# rs232RGBLEDController.net
KiCad netlist of a schematic drawn in EAGLE
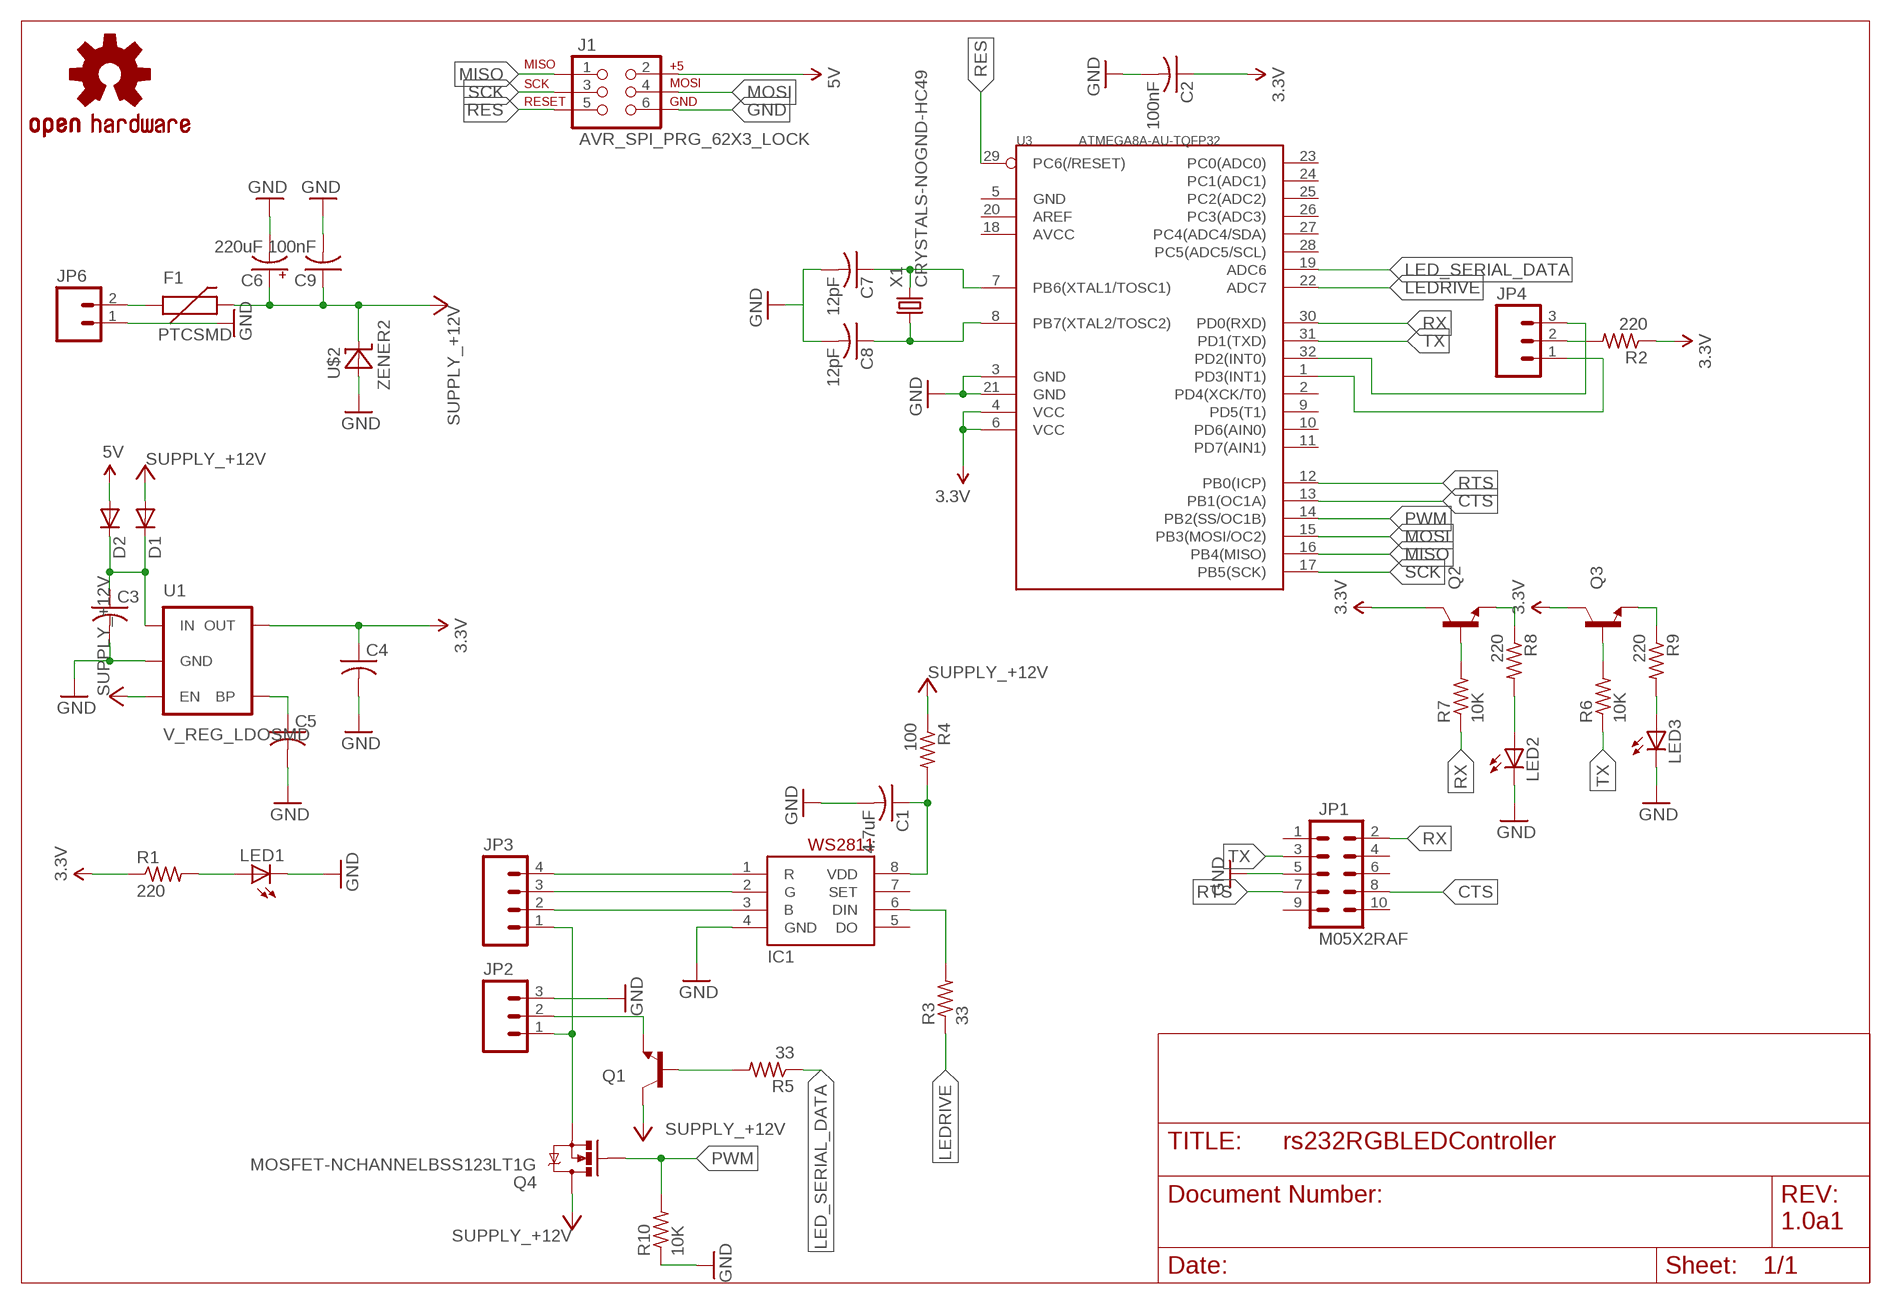
[diagram p0: schematic, sheet 1]

(export (version "E")
  (design (tool "Eeschema 10.0.6"))
  (components
    (comp (ref "C1")
      (value "4.7uF")
      (footprint "eagle-import:C0603")
      (libsource (lib "eagle-import") (part "C-USC0603"))
    )
    (comp (ref "C2")
      (value "100nF")
      (footprint "eagle-import:C0603")
      (libsource (lib "eagle-import") (part "C-USC0603"))
    )
    (comp (ref "C3")
      (value "C-USC0603")
      (footprint "eagle-import:C0603")
      (libsource (lib "eagle-import") (part "C-USC0603"))
    )
    (comp (ref "C4")
      (value "C-USC0603")
      (footprint "eagle-import:C0603")
      (libsource (lib "eagle-import") (part "C-USC0603"))
    )
    (comp (ref "C5")
      (value "C-USC0603")
      (footprint "eagle-import:C0603")
      (libsource (lib "eagle-import") (part "C-USC0603"))
    )
    (comp (ref "C6")
      (value "220uF")
      (footprint "eagle-import:175TMP-0810")
      (libsource (lib "eagle-import") (part "CPOL-US175TMP-0810"))
    )
    (comp (ref "C7")
      (value "12pF")
      (footprint "eagle-import:C0603")
      (libsource (lib "eagle-import") (part "C-USC0603"))
    )
    (comp (ref "C8")
      (value "12pF")
      (footprint "eagle-import:C0603")
      (libsource (lib "eagle-import") (part "C-USC0603"))
    )
    (comp (ref "C9")
      (value "100nF")
      (footprint "eagle-import:C0603")
      (libsource (lib "eagle-import") (part "C-USC0603"))
    )
    (comp (ref "D1")
      (value "DIODESOT23")
      (footprint "eagle-import:SOT23-3")
      (libsource (lib "eagle-import") (part "DIODESOT23"))
    )
    (comp (ref "D2")
      (value "DIODESOT23")
      (footprint "eagle-import:SOT23-3")
      (libsource (lib "eagle-import") (part "DIODESOT23"))
    )
    (comp (ref "F1")
      (value "PTCSMD")
      (footprint "eagle-import:PTC-1206")
      (libsource (lib "eagle-import") (part "PTCSMD"))
    )
    (comp (ref "IC1")
      (value "WS2811-SOP8")
      (footprint "eagle-import:SO08-SKINNYPADS")
      (libsource (lib "eagle-import") (part "WS2811-SOP8"))
    )
    (comp (ref "J1")
      (value "AVR_SPI_PRG_62X3_LOCK")
      (footprint "eagle-import:2X3_LOCK")
      (libsource (lib "eagle-import") (part "AVR_SPI_PRG_62X3_LOCK"))
    )
    (comp (ref "JP1")
      (value "M05X2RAF")
      (footprint "eagle-import:2X5-RAF")
      (libsource (lib "eagle-import") (part "M05X2RAF"))
    )
    (comp (ref "JP2")
      (value "M03PTH")
      (footprint "eagle-import:1X03")
      (libsource (lib "eagle-import") (part "M03PTH"))
    )
    (comp (ref "JP3")
      (value "M04PTH")
      (footprint "eagle-import:1X04")
      (libsource (lib "eagle-import") (part "M04PTH"))
    )
    (comp (ref "JP4")
      (value "M03PTH")
      (footprint "eagle-import:1X03")
      (libsource (lib "eagle-import") (part "M03PTH"))
    )
    (comp (ref "JP6")
      (value "M021X02_NO_SILK")
      (footprint "eagle-import:1X02_NO_SILK")
      (libsource (lib "eagle-import") (part "M021X02_NO_SILK"))
    )
    (comp (ref "LED1")
      (value "LED0603")
      (footprint "eagle-import:LED-0603")
      (libsource (lib "eagle-import") (part "LED0603"))
    )
    (comp (ref "LED2")
      (value "LED0603")
      (footprint "eagle-import:LED-0603")
      (libsource (lib "eagle-import") (part "LED0603"))
    )
    (comp (ref "LED3")
      (value "LED0603")
      (footprint "eagle-import:LED-0603")
      (libsource (lib "eagle-import") (part "LED0603"))
    )
    (comp (ref "Q1")
      (value "TRANSISTOR_NPNSOT23")
      (footprint "eagle-import:SOT23")
      (libsource (lib "eagle-import") (part "TRANSISTOR_NPNSOT23"))
    )
    (comp (ref "Q2")
      (value "TRANSISTOR_NPNSOT23")
      (footprint "eagle-import:SOT23")
      (libsource (lib "eagle-import") (part "TRANSISTOR_NPNSOT23"))
    )
    (comp (ref "Q3")
      (value "TRANSISTOR_NPNSOT23")
      (footprint "eagle-import:SOT23")
      (libsource (lib "eagle-import") (part "TRANSISTOR_NPNSOT23"))
    )
    (comp (ref "Q4")
      (value "MOSFET-NCHANNELBSS123LT1G")
      (footprint "eagle-import:SOT23-3")
      (libsource (lib "eagle-import") (part "MOSFET-NCHANNELBSS123LT1G"))
    )
    (comp (ref "R1")
      (value "220")
      (footprint "eagle-import:R0603")
      (libsource (lib "eagle-import") (part "R-US_R0603"))
    )
    (comp (ref "R2")
      (value "220")
      (footprint "eagle-import:R0603")
      (libsource (lib "eagle-import") (part "R-US_R0603"))
    )
    (comp (ref "R3")
      (value "33")
      (footprint "eagle-import:R0603")
      (libsource (lib "eagle-import") (part "R-US_R0603"))
    )
    (comp (ref "R4")
      (value "100")
      (footprint "eagle-import:R0603")
      (libsource (lib "eagle-import") (part "R-US_R0603"))
    )
    (comp (ref "R5")
      (value "33")
      (footprint "eagle-import:R0603")
      (libsource (lib "eagle-import") (part "R-US_R0603"))
    )
    (comp (ref "R6")
      (value "10K")
      (footprint "eagle-import:R0603")
      (libsource (lib "eagle-import") (part "R-US_R0603"))
    )
    (comp (ref "R7")
      (value "10K")
      (footprint "eagle-import:R0603")
      (libsource (lib "eagle-import") (part "R-US_R0603"))
    )
    (comp (ref "R8")
      (value "220")
      (footprint "eagle-import:R0603")
      (libsource (lib "eagle-import") (part "R-US_R0603"))
    )
    (comp (ref "R9")
      (value "220")
      (footprint "eagle-import:R0603")
      (libsource (lib "eagle-import") (part "R-US_R0603"))
    )
    (comp (ref "R10")
      (value "10K")
      (footprint "eagle-import:R0603")
      (libsource (lib "eagle-import") (part "R-US_R0603"))
    )
    (comp (ref "U$1")
      (value "OSHW-LOGOS")
      (footprint "eagle-import:OSHW-LOGO-S")
      (libsource (lib "eagle-import") (part "OSHW-LOGOS"))
    )
    (comp (ref "U$2")
      (value "ZENER2")
      (footprint "eagle-import:SOD123")
      (fields (field (name "SPICEPREFIX") "B"))
      (libsource (lib "eagle-import") (part "ZENER2"))
    )
    (comp (ref "U1")
      (value "V_REG_LDOSMD")
      (footprint "eagle-import:SOT23-5")
      (libsource (lib "eagle-import") (part "V_REG_LDOSMD"))
    )
    (comp (ref "U3")
      (value "ATMEGA8A-AU-TQFP32")
      (footprint "eagle-import:TQFP32-0.8-7X7MM")
      (fields (field (name "MPN") "ATMEGA8A-AU"))
      (libsource (lib "eagle-import") (part "MCU-ATMEGA8A-AU(TQFP32)"))
    )
    (comp (ref "X1")
      (value "CRYSTALS-NOGND-HC49")
      (footprint "eagle-import:HC49")
      (libsource (lib "eagle-import") (part "CRYSTALS-NOGND-HC49"))
    )
  )
  (nets
    (net (code "1") (name "3.3V") (class "Default")
      (node (ref "C2") (pin "1") (pinfunction "1_1") (pintype "passive"))
      (node (ref "C4") (pin "1") (pinfunction "1_1") (pintype "passive"))
      (node (ref "Q2") (pin "3") (pinfunction "C_3") (pintype "passive"))
      (node (ref "Q3") (pin "3") (pinfunction "C_3") (pintype "passive"))
      (node (ref "R1") (pin "1") (pinfunction "1_1") (pintype "passive"))
      (node (ref "R2") (pin "1") (pinfunction "1_1") (pintype "passive"))
      (node (ref "U1") (pin "5") (pinfunction "OUT_5") (pintype "passive"))
      (node (ref "U3") (pin "4") (pinfunction "VCC_4") (pintype "bidirectional"))
      (node (ref "U3") (pin "6") (pinfunction "VCC_6") (pintype "bidirectional"))
    )
    (net (code "2") (name "5V") (class "Default")
      (node (ref "D2") (pin "1") (pinfunction "A_1") (pintype "passive"))
      (node (ref "J1") (pin "2") (pinfunction "2_2") (pintype "passive"))
    )
    (net (code "3") (name "CTS") (class "Default")
      (node (ref "JP1") (pin "8") (pinfunction "8_8") (pintype "passive"))
      (node (ref "U3") (pin "13") (pinfunction "PB1(OC1A)_13") (pintype "bidirectional"))
    )
    (net (code "4") (name "GND") (class "Default")
      (node (ref "C1") (pin "2") (pinfunction "2_2") (pintype "passive"))
      (node (ref "C2") (pin "2") (pinfunction "2_2") (pintype "passive"))
      (node (ref "C3") (pin "2") (pinfunction "2_2") (pintype "passive"))
      (node (ref "C4") (pin "2") (pinfunction "2_2") (pintype "passive"))
      (node (ref "C5") (pin "2") (pinfunction "2_2") (pintype "passive"))
      (node (ref "C6") (pin "-") (pinfunction "-_-") (pintype "passive"))
      (node (ref "C7") (pin "2") (pinfunction "2_2") (pintype "passive"))
      (node (ref "C8") (pin "2") (pinfunction "2_2") (pintype "passive"))
      (node (ref "C9") (pin "2") (pinfunction "2_2") (pintype "passive"))
      (node (ref "IC1") (pin "4") (pinfunction "GND_4") (pintype "power_in"))
      (node (ref "J1") (pin "6") (pinfunction "6_6") (pintype "passive"))
      (node (ref "JP1") (pin "5") (pinfunction "5_5") (pintype "passive"))
      (node (ref "JP2") (pin "3") (pinfunction "3_3") (pintype "passive"))
      (node (ref "JP6") (pin "1") (pinfunction "1_1") (pintype "passive"))
      (node (ref "LED1") (pin "C") (pinfunction "C_C") (pintype "passive"))
      (node (ref "LED2") (pin "C") (pinfunction "C_C") (pintype "passive"))
      (node (ref "LED3") (pin "C") (pinfunction "C_C") (pintype "passive"))
      (node (ref "R10") (pin "1") (pinfunction "1_1") (pintype "passive"))
      (node (ref "U$2") (pin "A") (pinfunction "A_A") (pintype "passive"))
      (node (ref "U1") (pin "2") (pinfunction "GND_2") (pintype "input"))
      (node (ref "U3") (pin "21") (pinfunction "GND_21") (pintype "bidirectional"))
      (node (ref "U3") (pin "3") (pinfunction "GND_3") (pintype "bidirectional"))
    )
    (net (code "5") (name "LEDRIVE") (class "Default")
      (node (ref "R3") (pin "1") (pinfunction "1_1") (pintype "passive"))
      (node (ref "U3") (pin "22") (pinfunction "ADC7_22") (pintype "bidirectional"))
    )
    (net (code "6") (name "LED_SERIAL_DATA") (class "Default")
      (node (ref "R5") (pin "1") (pinfunction "1_1") (pintype "passive"))
      (node (ref "U3") (pin "19") (pinfunction "ADC6_19") (pintype "bidirectional"))
    )
    (net (code "7") (name "MISO") (class "Default")
      (node (ref "J1") (pin "1") (pinfunction "1_1") (pintype "passive"))
      (node (ref "U3") (pin "16") (pinfunction "PB4(MISO)_16") (pintype "bidirectional"))
    )
    (net (code "8") (name "MOSI") (class "Default")
      (node (ref "J1") (pin "4") (pinfunction "4_4") (pintype "passive"))
      (node (ref "U3") (pin "15") (pinfunction "PB3(MOSI/OC2)_15") (pintype "bidirectional"))
    )
    (net (code "9") (name "Net-(D1-C)") (class "Default")
      (node (ref "C3") (pin "1") (pinfunction "1_1") (pintype "passive"))
      (node (ref "D1") (pin "3") (pinfunction "C_3") (pintype "passive"))
      (node (ref "D2") (pin "3") (pinfunction "C_3") (pintype "passive"))
      (node (ref "U1") (pin "1") (pinfunction "IN_1") (pintype "input"))
    )
    (net (code "10") (name "Net-(F1-Pad1)") (class "Default")
      (node (ref "F1") (pin "1") (pinfunction "1_1") (pintype "bidirectional"))
      (node (ref "JP6") (pin "2") (pinfunction "2_2") (pintype "passive"))
    )
    (net (code "11") (name "Net-(IC1-B)") (class "Default")
      (node (ref "IC1") (pin "3") (pinfunction "B_3") (pintype "open_collector"))
      (node (ref "JP3") (pin "2") (pinfunction "2_2") (pintype "passive"))
    )
    (net (code "12") (name "Net-(IC1-DIN)") (class "Default")
      (node (ref "IC1") (pin "6") (pinfunction "DIN_6") (pintype "input"))
      (node (ref "R3") (pin "2") (pinfunction "2_2") (pintype "passive"))
    )
    (net (code "13") (name "Net-(IC1-G)") (class "Default")
      (node (ref "IC1") (pin "2") (pinfunction "G_2") (pintype "open_collector"))
      (node (ref "JP3") (pin "3") (pinfunction "3_3") (pintype "passive"))
    )
    (net (code "14") (name "Net-(IC1-R)") (class "Default")
      (node (ref "IC1") (pin "1") (pinfunction "R_1") (pintype "open_collector"))
      (node (ref "JP3") (pin "4") (pinfunction "4_4") (pintype "passive"))
    )
    (net (code "15") (name "Net-(IC1-VDD)") (class "Default")
      (node (ref "C1") (pin "1") (pinfunction "1_1") (pintype "passive"))
      (node (ref "IC1") (pin "8") (pinfunction "VDD_8") (pintype "power_in"))
      (node (ref "R4") (pin "2") (pinfunction "2_2") (pintype "passive"))
    )
    (net (code "16") (name "Net-(JP4-Pad2)") (class "Default")
      (node (ref "JP4") (pin "2") (pinfunction "2_2") (pintype "passive"))
      (node (ref "R2") (pin "2") (pinfunction "2_2") (pintype "passive"))
    )
    (net (code "17") (name "Net-(LED1-PadA)") (class "Default")
      (node (ref "LED1") (pin "A") (pinfunction "A_A") (pintype "passive"))
      (node (ref "R1") (pin "2") (pinfunction "2_2") (pintype "passive"))
    )
    (net (code "18") (name "Net-(LED2-PadA)") (class "Default")
      (node (ref "LED2") (pin "A") (pinfunction "A_A") (pintype "passive"))
      (node (ref "R8") (pin "2") (pinfunction "2_2") (pintype "passive"))
    )
    (net (code "19") (name "Net-(LED3-PadA)") (class "Default")
      (node (ref "LED3") (pin "A") (pinfunction "A_A") (pintype "passive"))
      (node (ref "R9") (pin "2") (pinfunction "2_2") (pintype "passive"))
    )
    (net (code "20") (name "Net-(Q1-B)") (class "Default")
      (node (ref "Q1") (pin "1") (pinfunction "B_1") (pintype "passive"))
      (node (ref "R5") (pin "2") (pinfunction "2_2") (pintype "passive"))
    )
    (net (code "21") (name "Net-(Q1-E)") (class "Default")
      (node (ref "JP2") (pin "2") (pinfunction "2_2") (pintype "passive"))
      (node (ref "Q1") (pin "2") (pinfunction "E_2") (pintype "passive"))
    )
    (net (code "22") (name "Net-(Q2-B)") (class "Default")
      (node (ref "Q2") (pin "1") (pinfunction "B_1") (pintype "passive"))
      (node (ref "R7") (pin "2") (pinfunction "2_2") (pintype "passive"))
    )
    (net (code "23") (name "Net-(Q2-E)") (class "Default")
      (node (ref "Q2") (pin "2") (pinfunction "E_2") (pintype "passive"))
      (node (ref "R8") (pin "1") (pinfunction "1_1") (pintype "passive"))
    )
    (net (code "24") (name "Net-(Q3-B)") (class "Default")
      (node (ref "Q3") (pin "1") (pinfunction "B_1") (pintype "passive"))
      (node (ref "R6") (pin "2") (pinfunction "2_2") (pintype "passive"))
    )
    (net (code "25") (name "Net-(Q3-E)") (class "Default")
      (node (ref "Q3") (pin "2") (pinfunction "E_2") (pintype "passive"))
      (node (ref "R9") (pin "1") (pinfunction "1_1") (pintype "passive"))
    )
    (net (code "26") (name "Net-(Q4-S)") (class "Default")
      (node (ref "JP2") (pin "1") (pinfunction "1_1") (pintype "passive"))
      (node (ref "JP3") (pin "1") (pinfunction "1_1") (pintype "passive"))
      (node (ref "Q4") (pin "2") (pinfunction "S_2") (pintype "passive"))
    )
    (net (code "27") (name "Net-(U1-BP)") (class "Default")
      (node (ref "C5") (pin "1") (pinfunction "1_1") (pintype "passive"))
      (node (ref "U1") (pin "4") (pinfunction "BP_4") (pintype "input"))
    )
    (net (code "28") (name "Net-(U3-PB6(XTAL1{slash}TOSC1))") (class "Default")
      (node (ref "C7") (pin "1") (pinfunction "1_1") (pintype "passive"))
      (node (ref "U3") (pin "7") (pinfunction "PB6(XTAL1/TOSC1)_7") (pintype "bidirectional"))
      (node (ref "X1") (pin "2") (pinfunction "2_2") (pintype "passive"))
    )
    (net (code "29") (name "Net-(U3-PB7(XTAL2{slash}TOSC2))") (class "Default")
      (node (ref "C8") (pin "1") (pinfunction "1_1") (pintype "passive"))
      (node (ref "U3") (pin "8") (pinfunction "PB7(XTAL2/TOSC2)_8") (pintype "bidirectional"))
      (node (ref "X1") (pin "1") (pinfunction "1_1") (pintype "passive"))
    )
    (net (code "30") (name "Net-(U3-PD2(INT0))") (class "Default")
      (node (ref "JP4") (pin "3") (pinfunction "3_3") (pintype "passive"))
      (node (ref "U3") (pin "32") (pinfunction "PD2(INT0)_32") (pintype "bidirectional"))
    )
    (net (code "31") (name "Net-(U3-PD3(INT1))") (class "Default")
      (node (ref "JP4") (pin "1") (pinfunction "1_1") (pintype "passive"))
      (node (ref "U3") (pin "1") (pinfunction "PD3(INT1)_1") (pintype "bidirectional"))
    )
    (net (code "32") (name "PWM") (class "Default")
      (node (ref "Q4") (pin "1") (pinfunction "G_1") (pintype "passive"))
      (node (ref "R10") (pin "2") (pinfunction "2_2") (pintype "passive"))
      (node (ref "U3") (pin "14") (pinfunction "PB2(SS/OC1B)_14") (pintype "bidirectional"))
    )
    (net (code "33") (name "RES") (class "Default")
      (node (ref "J1") (pin "5") (pinfunction "5_5") (pintype "passive"))
      (node (ref "U3") (pin "29") (pinfunction "PC6(/RESET)_29") (pintype "bidirectional"))
    )
    (net (code "34") (name "RTS") (class "Default")
      (node (ref "JP1") (pin "7") (pinfunction "7_7") (pintype "passive"))
      (node (ref "U3") (pin "12") (pinfunction "PB0(ICP)_12") (pintype "bidirectional"))
    )
    (net (code "35") (name "RX") (class "Default")
      (node (ref "JP1") (pin "2") (pinfunction "2_2") (pintype "passive"))
      (node (ref "R7") (pin "1") (pinfunction "1_1") (pintype "passive"))
      (node (ref "U3") (pin "30") (pinfunction "PD0(RXD)_30") (pintype "bidirectional"))
    )
    (net (code "36") (name "SCK") (class "Default")
      (node (ref "J1") (pin "3") (pinfunction "3_3") (pintype "passive"))
      (node (ref "U3") (pin "17") (pinfunction "PB5(SCK)_17") (pintype "bidirectional"))
    )
    (net (code "37") (name "SUPPLY_+12V") (class "Default")
      (node (ref "C6") (pin "+") (pinfunction "+_+") (pintype "passive"))
      (node (ref "C9") (pin "1") (pinfunction "1_1") (pintype "passive"))
      (node (ref "D1") (pin "1") (pinfunction "A_1") (pintype "passive"))
      (node (ref "F1") (pin "2") (pinfunction "2_2") (pintype "bidirectional"))
      (node (ref "Q1") (pin "3") (pinfunction "C_3") (pintype "passive"))
      (node (ref "Q4") (pin "3") (pinfunction "D_3") (pintype "passive"))
      (node (ref "R4") (pin "1") (pinfunction "1_1") (pintype "passive"))
      (node (ref "U$2") (pin "C") (pinfunction "C_C") (pintype "passive"))
      (node (ref "U1") (pin "3") (pinfunction "EN_3") (pintype "input"))
    )
    (net (code "38") (name "TX") (class "Default")
      (node (ref "JP1") (pin "3") (pinfunction "3_3") (pintype "passive"))
      (node (ref "R6") (pin "1") (pinfunction "1_1") (pintype "passive"))
      (node (ref "U3") (pin "31") (pinfunction "PD1(TXD)_31") (pintype "bidirectional"))
    )
    (net (code "39") (name "unconnected-(IC1-DO-Pad5)") (class "Default")
      (node (ref "IC1") (pin "5") (pinfunction "DO_5") (pintype "output"))
    )
    (net (code "40") (name "unconnected-(IC1-SET-Pad7)") (class "Default")
      (node (ref "IC1") (pin "7") (pinfunction "SET_7") (pintype "input"))
    )
    (net (code "41") (name "unconnected-(JP1-Pad1)") (class "Default")
      (node (ref "JP1") (pin "1") (pinfunction "1_1") (pintype "passive"))
    )
    (net (code "42") (name "unconnected-(JP1-Pad4)") (class "Default")
      (node (ref "JP1") (pin "4") (pinfunction "4_4") (pintype "passive"))
    )
    (net (code "43") (name "unconnected-(JP1-Pad6)") (class "Default")
      (node (ref "JP1") (pin "6") (pinfunction "6_6") (pintype "passive"))
    )
    (net (code "44") (name "unconnected-(JP1-Pad9)") (class "Default")
      (node (ref "JP1") (pin "9") (pinfunction "9_9") (pintype "passive"))
    )
    (net (code "45") (name "unconnected-(JP1-Pad10)") (class "Default")
      (node (ref "JP1") (pin "10") (pinfunction "10_10") (pintype "passive"))
    )
    (net (code "46") (name "unconnected-(U3-AREF-Pad20)") (class "Default")
      (node (ref "U3") (pin "20") (pinfunction "AREF_20") (pintype "bidirectional"))
    )
    (net (code "47") (name "unconnected-(U3-AVCC-Pad18)") (class "Default")
      (node (ref "U3") (pin "18") (pinfunction "AVCC_18") (pintype "bidirectional"))
    )
    (net (code "48") (name "unconnected-(U3-GND-Pad5)") (class "Default")
      (node (ref "U3") (pin "5") (pinfunction "GND_5") (pintype "bidirectional"))
    )
    (net (code "49") (name "unconnected-(U3-PC0(ADC0)-Pad23)") (class "Default")
      (node (ref "U3") (pin "23") (pinfunction "PC0(ADC0)_23") (pintype "bidirectional"))
    )
    (net (code "50") (name "unconnected-(U3-PC1(ADC1)-Pad24)") (class "Default")
      (node (ref "U3") (pin "24") (pinfunction "PC1(ADC1)_24") (pintype "bidirectional"))
    )
    (net (code "51") (name "unconnected-(U3-PC2(ADC2)-Pad25)") (class "Default")
      (node (ref "U3") (pin "25") (pinfunction "PC2(ADC2)_25") (pintype "bidirectional"))
    )
    (net (code "52") (name "unconnected-(U3-PC3(ADC3)-Pad26)") (class "Default")
      (node (ref "U3") (pin "26") (pinfunction "PC3(ADC3)_26") (pintype "bidirectional"))
    )
    (net (code "53") (name "unconnected-(U3-PC4(ADC4{slash}SDA)-Pad27)") (class "Default")
      (node (ref "U3") (pin "27") (pinfunction "PC4(ADC4/SDA)_27") (pintype "bidirectional"))
    )
    (net (code "54") (name "unconnected-(U3-PC5(ADC5{slash}SCL)-Pad28)") (class "Default")
      (node (ref "U3") (pin "28") (pinfunction "PC5(ADC5/SCL)_28") (pintype "bidirectional"))
    )
    (net (code "55") (name "unconnected-(U3-PD4(XCK{slash}T0)-Pad2)") (class "Default")
      (node (ref "U3") (pin "2") (pinfunction "PD4(XCK/T0)_2") (pintype "bidirectional"))
    )
    (net (code "56") (name "unconnected-(U3-PD5(T1)-Pad9)") (class "Default")
      (node (ref "U3") (pin "9") (pinfunction "PD5(T1)_9") (pintype "bidirectional"))
    )
    (net (code "57") (name "unconnected-(U3-PD6(AIN0)-Pad10)") (class "Default")
      (node (ref "U3") (pin "10") (pinfunction "PD6(AIN0)_10") (pintype "bidirectional"))
    )
    (net (code "58") (name "unconnected-(U3-PD7(AIN1)-Pad11)") (class "Default")
      (node (ref "U3") (pin "11") (pinfunction "PD7(AIN1)_11") (pintype "bidirectional"))
    )
  )
)
